# bbaudio.net
KiCad netlist of a schematic drawn in EAGLE
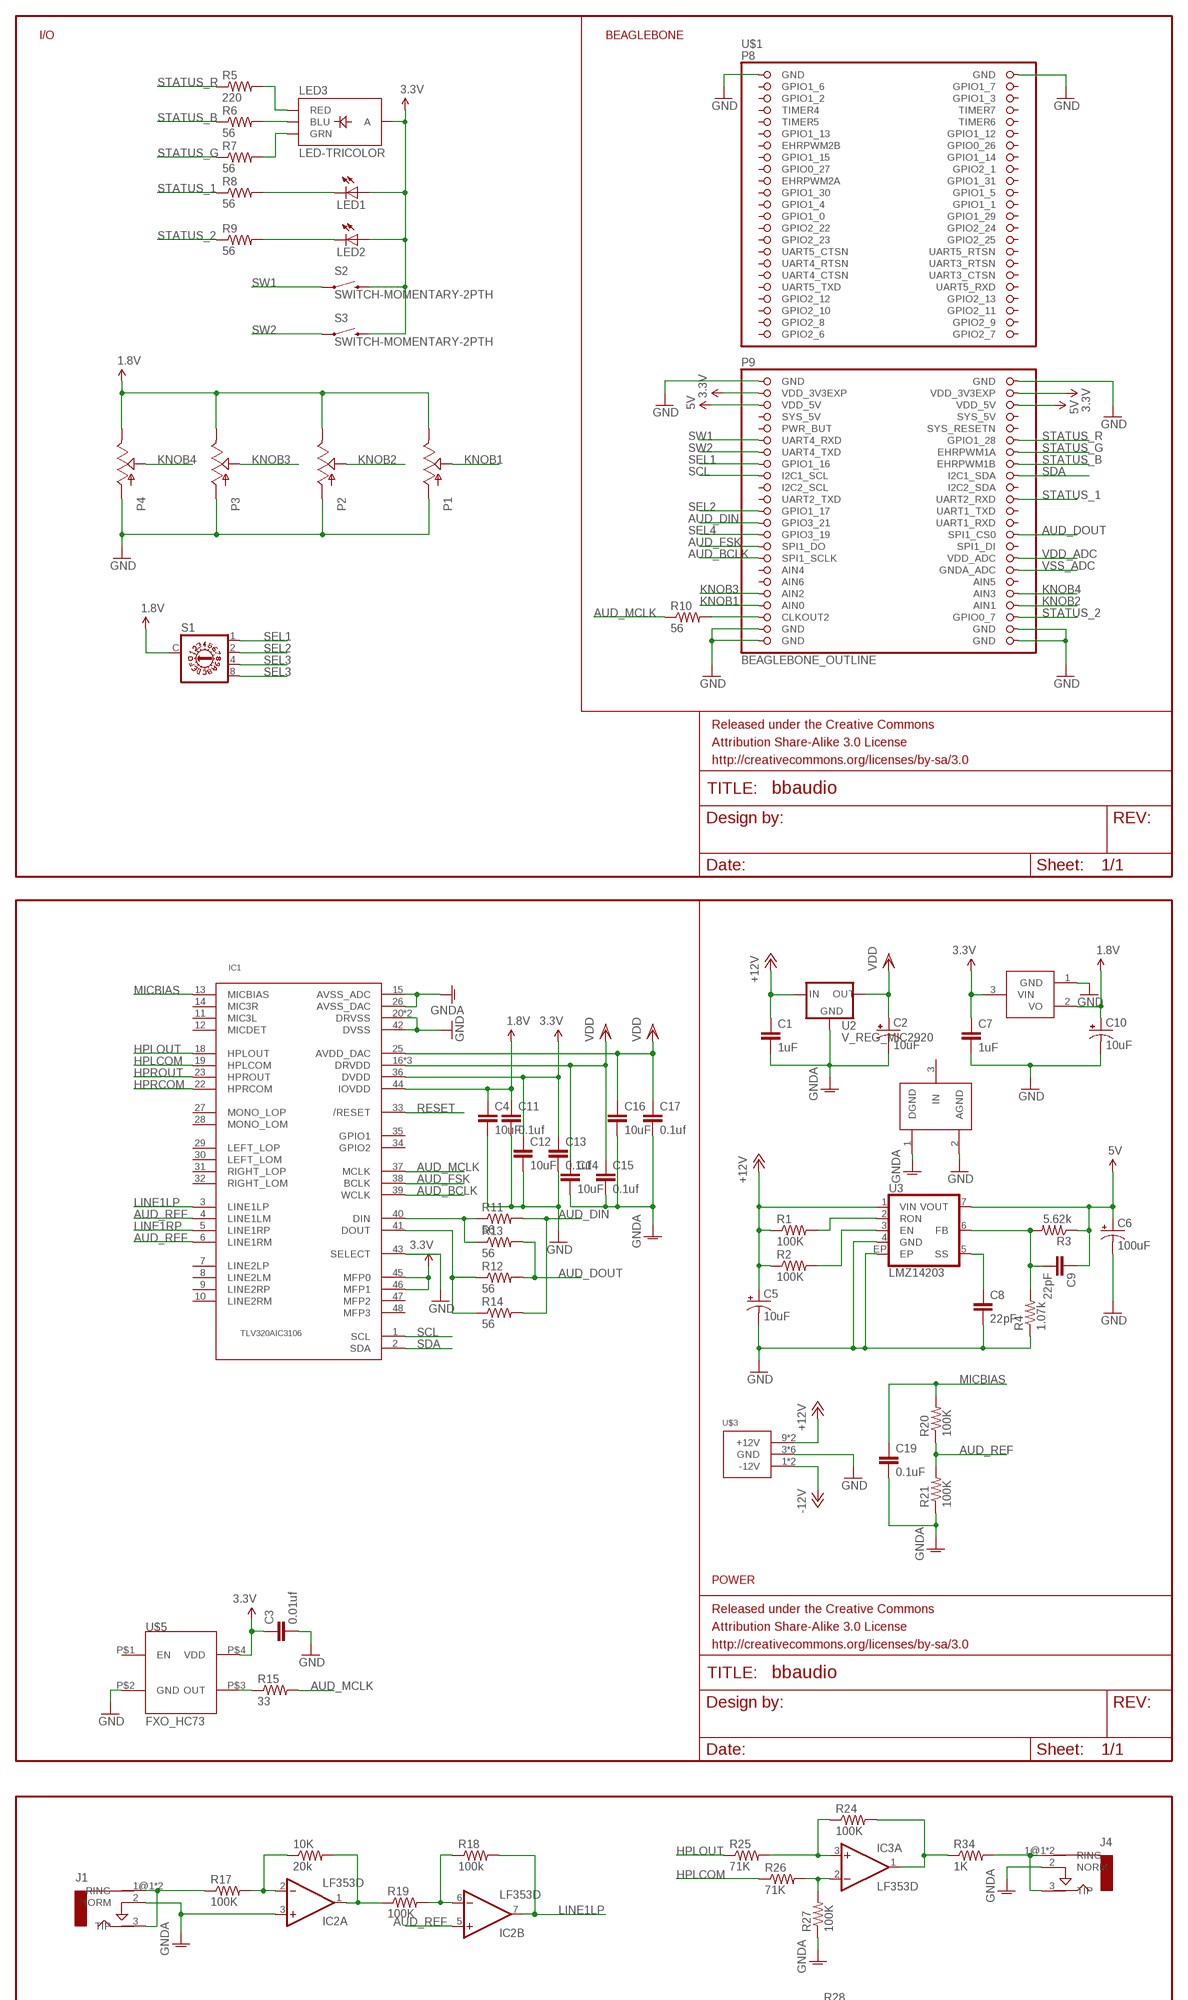
[diagram p0: schematic, sheet 1, part 1 of 2]
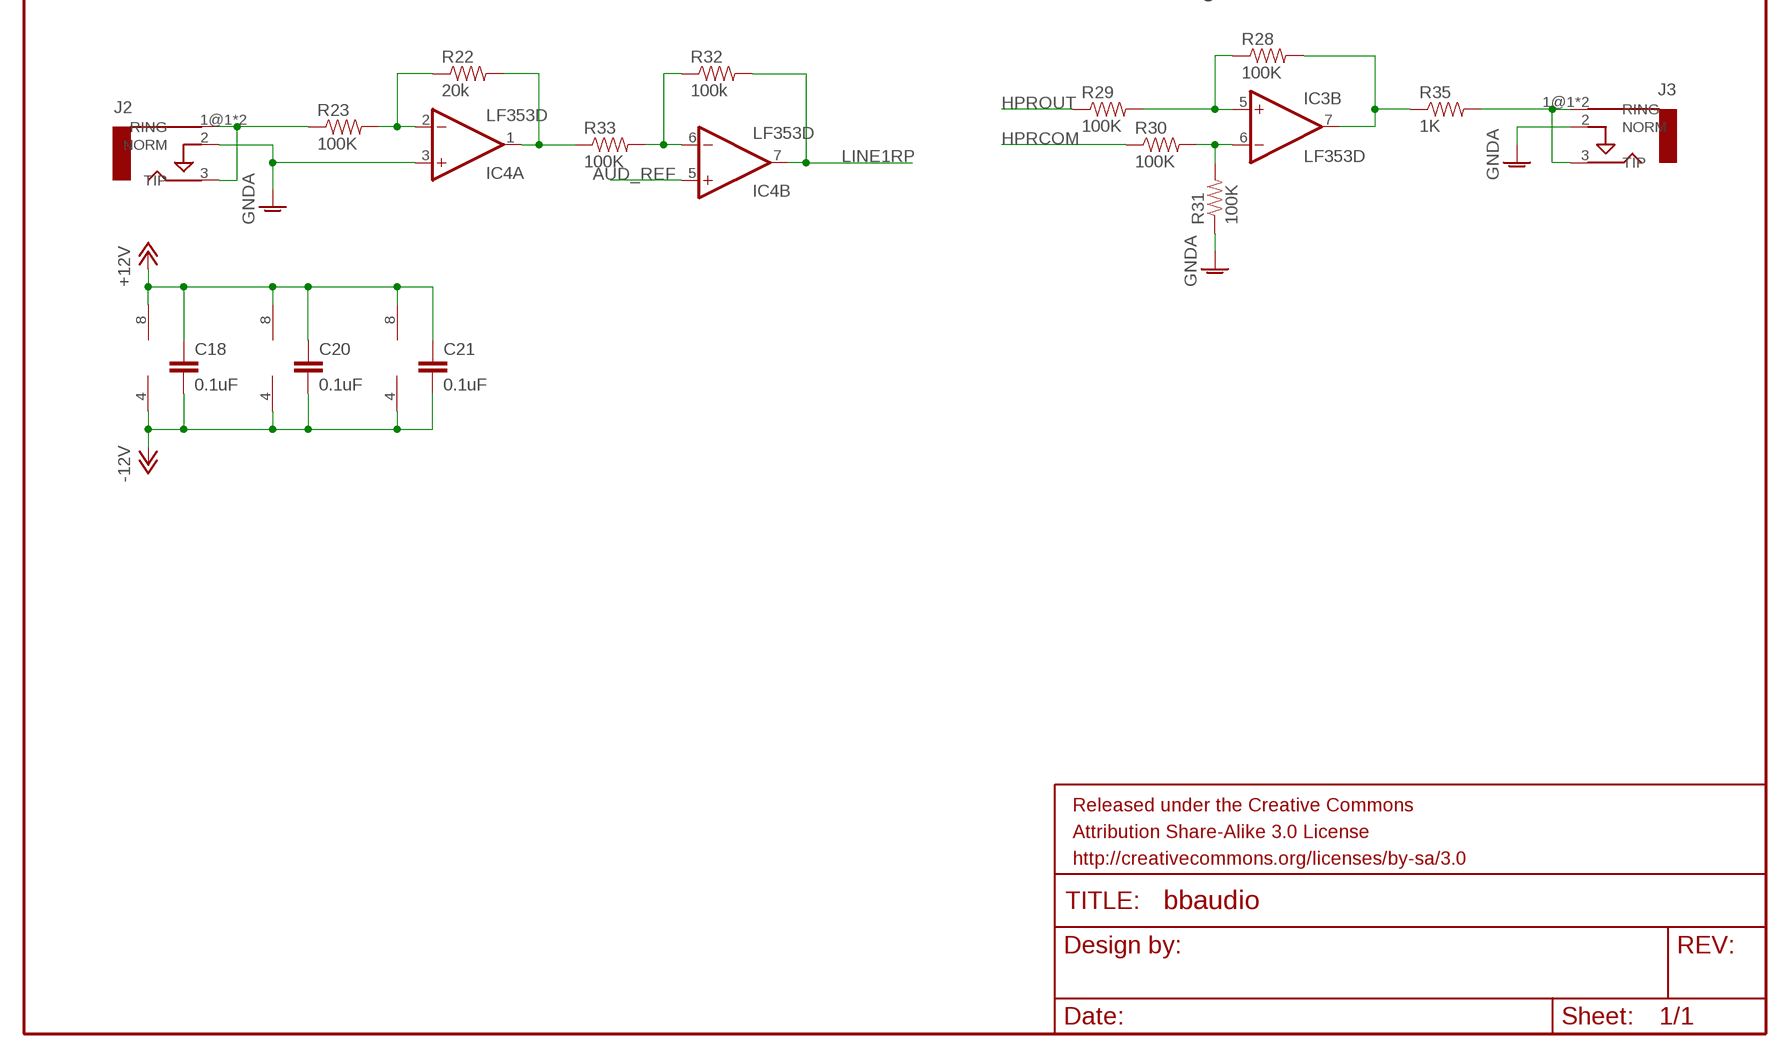
[diagram p1: schematic, sheet 1, part 2 of 2]

(export (version "E")
  (design (tool "Eeschema 10.0.6"))
  (components
    (comp (ref "10K")
      (value "20k")
      (footprint "eagle-import:0603-RES")
      (libsource (lib "eagle-import") (part "RESISTOR0603-RES"))
    )
    (comp (ref "C1")
      (value "1uF")
      (footprint "eagle-import:C0603")
      (libsource (lib "eagle-import") (part "C-EUC0603"))
    )
    (comp (ref "C2")
      (value "10uF")
      (footprint "eagle-import:EIA3216")
      (libsource (lib "eagle-import") (part "CAP_POL1206"))
    )
    (comp (ref "C3")
      (value "0.01uf")
      (footprint "eagle-import:C0603")
      (libsource (lib "eagle-import") (part "C-EUC0603"))
    )
    (comp (ref "C4")
      (value "10uF")
      (footprint "eagle-import:C0603")
      (libsource (lib "eagle-import") (part "C-EUC0603"))
    )
    (comp (ref "C5")
      (value "10uF")
      (footprint "eagle-import:EIA3216")
      (libsource (lib "eagle-import") (part "CAP_POL1206"))
    )
    (comp (ref "C6")
      (value "100uF")
      (footprint "eagle-import:EIA3216")
      (libsource (lib "eagle-import") (part "CAP_POL1206"))
    )
    (comp (ref "C7")
      (value "1uF")
      (footprint "eagle-import:C0603")
      (libsource (lib "eagle-import") (part "C-EUC0603"))
    )
    (comp (ref "C8")
      (value "22pF")
      (footprint "eagle-import:C0603")
      (libsource (lib "eagle-import") (part "C-EUC0603"))
    )
    (comp (ref "C9")
      (value "22pF")
      (footprint "eagle-import:C0603")
      (libsource (lib "eagle-import") (part "C-EUC0603"))
    )
    (comp (ref "C10")
      (value "10uF")
      (footprint "eagle-import:EIA3216")
      (libsource (lib "eagle-import") (part "CAP_POL1206"))
    )
    (comp (ref "C11")
      (value "0.1uf")
      (footprint "eagle-import:C0603")
      (libsource (lib "eagle-import") (part "C-EUC0603"))
    )
    (comp (ref "C12")
      (value "10uF")
      (footprint "eagle-import:C0603")
      (libsource (lib "eagle-import") (part "C-EUC0603"))
    )
    (comp (ref "C13")
      (value "0.1uf")
      (footprint "eagle-import:C0603")
      (libsource (lib "eagle-import") (part "C-EUC0603"))
    )
    (comp (ref "C14")
      (value "10uF")
      (footprint "eagle-import:C0603")
      (libsource (lib "eagle-import") (part "C-EUC0603"))
    )
    (comp (ref "C15")
      (value "0.1uf")
      (footprint "eagle-import:C0603")
      (libsource (lib "eagle-import") (part "C-EUC0603"))
    )
    (comp (ref "C16")
      (value "10uF")
      (footprint "eagle-import:C0603")
      (libsource (lib "eagle-import") (part "C-EUC0603"))
    )
    (comp (ref "C17")
      (value "0.1uf")
      (footprint "eagle-import:C0603")
      (libsource (lib "eagle-import") (part "C-EUC0603"))
    )
    (comp (ref "C18")
      (value "0.1uF")
      (footprint "eagle-import:C0603")
      (libsource (lib "eagle-import") (part "C-EUC0603"))
    )
    (comp (ref "C19")
      (value "0.1uF")
      (footprint "eagle-import:C0603")
      (libsource (lib "eagle-import") (part "C-EUC0603"))
    )
    (comp (ref "C20")
      (value "0.1uF")
      (footprint "eagle-import:C0603")
      (libsource (lib "eagle-import") (part "C-EUC0603"))
    )
    (comp (ref "C21")
      (value "0.1uF")
      (footprint "eagle-import:C0603")
      (libsource (lib "eagle-import") (part "C-EUC0603"))
    )
    (comp (ref "IC1")
      (value "TLV320AIC3106")
      (footprint "eagle-import:QFN48")
      (libsource (lib "eagle-import") (part "TLV320AIC3106"))
    )
    (comp (ref "IC2")
      (value "LF353D")
      (footprint "eagle-import:SO08")
      (libsource (lib "eagle-import") (part "LF353D"))
    )
    (comp (ref "IC3")
      (value "LF353D")
      (footprint "eagle-import:SO08")
      (libsource (lib "eagle-import") (part "LF353D"))
    )
    (comp (ref "IC4")
      (value "LF353D")
      (footprint "eagle-import:SO08")
      (libsource (lib "eagle-import") (part "LF353D"))
    )
    (comp (ref "J1")
      (value "AUDIO-JACKERTHENVAR")
      (footprint "eagle-import:ERTHENVAR-JACK")
      (libsource (lib "eagle-import") (part "AUDIO-JACKERTHENVAR"))
    )
    (comp (ref "J2")
      (value "AUDIO-JACKERTHENVAR")
      (footprint "eagle-import:ERTHENVAR-JACK")
      (libsource (lib "eagle-import") (part "AUDIO-JACKERTHENVAR"))
    )
    (comp (ref "J3")
      (value "AUDIO-JACKERTHENVAR")
      (footprint "eagle-import:ERTHENVAR-JACK")
      (libsource (lib "eagle-import") (part "AUDIO-JACKERTHENVAR"))
    )
    (comp (ref "J4")
      (value "AUDIO-JACKERTHENVAR")
      (footprint "eagle-import:ERTHENVAR-JACK")
      (libsource (lib "eagle-import") (part "AUDIO-JACKERTHENVAR"))
    )
    (comp (ref "LED1")
      (value "LED-FKIT-1206")
      (footprint "eagle-import:FKIT-LED-1206")
      (libsource (lib "eagle-import") (part "LED-FKIT-1206"))
    )
    (comp (ref "LED2")
      (value "LED-FKIT-1206")
      (footprint "eagle-import:FKIT-LED-1206")
      (libsource (lib "eagle-import") (part "LED-FKIT-1206"))
    )
    (comp (ref "LED3")
      (value "LED-TRICOLOR")
      (footprint "eagle-import:LED-TRICOLOR-SMD")
      (libsource (lib "eagle-import") (part "LED-TRICOLOR"))
    )
    (comp (ref "P1")
      (value "SPARKFUN_POTPDB12")
      (footprint "eagle-import:SPARKFUN_PDB12")
      (libsource (lib "eagle-import") (part "SPARKFUN_POTPDB12"))
    )
    (comp (ref "P2")
      (value "SPARKFUN_POTPDB12")
      (footprint "eagle-import:SPARKFUN_PDB12")
      (libsource (lib "eagle-import") (part "SPARKFUN_POTPDB12"))
    )
    (comp (ref "P3")
      (value "SPARKFUN_POTPDB12")
      (footprint "eagle-import:SPARKFUN_PDB12")
      (libsource (lib "eagle-import") (part "SPARKFUN_POTPDB12"))
    )
    (comp (ref "P4")
      (value "SPARKFUN_POTPDB12")
      (footprint "eagle-import:SPARKFUN_PDB12")
      (libsource (lib "eagle-import") (part "SPARKFUN_POTPDB12"))
    )
    (comp (ref "R1")
      (value "100K")
      (footprint "eagle-import:0603-RES")
      (libsource (lib "eagle-import") (part "RESISTOR0603-RES"))
    )
    (comp (ref "R2")
      (value "100K")
      (footprint "eagle-import:0603-RES")
      (libsource (lib "eagle-import") (part "RESISTOR0603-RES"))
    )
    (comp (ref "R3")
      (value "5.62k")
      (footprint "eagle-import:0603-RES")
      (libsource (lib "eagle-import") (part "RESISTOR0603-RES"))
    )
    (comp (ref "R4")
      (value "1.07k")
      (footprint "eagle-import:0603-RES")
      (libsource (lib "eagle-import") (part "RESISTOR0603-RES"))
    )
    (comp (ref "R5")
      (value "220")
      (footprint "eagle-import:0603-RES")
      (libsource (lib "eagle-import") (part "RESISTOR0603-RES"))
    )
    (comp (ref "R6")
      (value "56")
      (footprint "eagle-import:0603-RES")
      (libsource (lib "eagle-import") (part "RESISTOR0603-RES"))
    )
    (comp (ref "R7")
      (value "56")
      (footprint "eagle-import:0603-RES")
      (libsource (lib "eagle-import") (part "RESISTOR0603-RES"))
    )
    (comp (ref "R8")
      (value "56")
      (footprint "eagle-import:0603-RES")
      (libsource (lib "eagle-import") (part "RESISTOR0603-RES"))
    )
    (comp (ref "R9")
      (value "56")
      (footprint "eagle-import:0603-RES")
      (libsource (lib "eagle-import") (part "RESISTOR0603-RES"))
    )
    (comp (ref "R10")
      (value "56")
      (footprint "eagle-import:0603-RES")
      (libsource (lib "eagle-import") (part "RESISTOR0603-RES"))
    )
    (comp (ref "R11")
      (value "56")
      (footprint "eagle-import:0603-RES")
      (libsource (lib "eagle-import") (part "RESISTOR0603-RES"))
    )
    (comp (ref "R12")
      (value "56")
      (footprint "eagle-import:0603-RES")
      (libsource (lib "eagle-import") (part "RESISTOR0603-RES"))
    )
    (comp (ref "R13")
      (value "56")
      (footprint "eagle-import:0603-RES")
      (libsource (lib "eagle-import") (part "RESISTOR0603-RES"))
    )
    (comp (ref "R14")
      (value "56")
      (footprint "eagle-import:0603-RES")
      (libsource (lib "eagle-import") (part "RESISTOR0603-RES"))
    )
    (comp (ref "R15")
      (value "33")
      (footprint "eagle-import:0603-RES")
      (libsource (lib "eagle-import") (part "RESISTOR0603-RES"))
    )
    (comp (ref "R17")
      (value "100K")
      (footprint "eagle-import:0603-RES")
      (libsource (lib "eagle-import") (part "RESISTOR0603-RES"))
    )
    (comp (ref "R18")
      (value "100k")
      (footprint "eagle-import:0603-RES")
      (libsource (lib "eagle-import") (part "RESISTOR0603-RES"))
    )
    (comp (ref "R19")
      (value "100K")
      (footprint "eagle-import:0603-RES")
      (libsource (lib "eagle-import") (part "RESISTOR0603-RES"))
    )
    (comp (ref "R20")
      (value "100K")
      (footprint "eagle-import:0603-RES")
      (libsource (lib "eagle-import") (part "RESISTOR0603-RES"))
    )
    (comp (ref "R21")
      (value "100K")
      (footprint "eagle-import:0603-RES")
      (libsource (lib "eagle-import") (part "RESISTOR0603-RES"))
    )
    (comp (ref "R22")
      (value "20k")
      (footprint "eagle-import:0603-RES")
      (libsource (lib "eagle-import") (part "RESISTOR0603-RES"))
    )
    (comp (ref "R23")
      (value "100K")
      (footprint "eagle-import:0603-RES")
      (libsource (lib "eagle-import") (part "RESISTOR0603-RES"))
    )
    (comp (ref "R24")
      (value "100K")
      (footprint "eagle-import:0603-RES")
      (libsource (lib "eagle-import") (part "RESISTOR0603-RES"))
    )
    (comp (ref "R25")
      (value "71K")
      (footprint "eagle-import:0603-RES")
      (libsource (lib "eagle-import") (part "RESISTOR0603-RES"))
    )
    (comp (ref "R26")
      (value "71K")
      (footprint "eagle-import:0603-RES")
      (libsource (lib "eagle-import") (part "RESISTOR0603-RES"))
    )
    (comp (ref "R27")
      (value "100K")
      (footprint "eagle-import:0603-RES")
      (libsource (lib "eagle-import") (part "RESISTOR0603-RES"))
    )
    (comp (ref "R28")
      (value "100K")
      (footprint "eagle-import:0603-RES")
      (libsource (lib "eagle-import") (part "RESISTOR0603-RES"))
    )
    (comp (ref "R29")
      (value "100K")
      (footprint "eagle-import:0603-RES")
      (libsource (lib "eagle-import") (part "RESISTOR0603-RES"))
    )
    (comp (ref "R30")
      (value "100K")
      (footprint "eagle-import:0603-RES")
      (libsource (lib "eagle-import") (part "RESISTOR0603-RES"))
    )
    (comp (ref "R31")
      (value "100K")
      (footprint "eagle-import:0603-RES")
      (libsource (lib "eagle-import") (part "RESISTOR0603-RES"))
    )
    (comp (ref "R32")
      (value "100k")
      (footprint "eagle-import:0603-RES")
      (libsource (lib "eagle-import") (part "RESISTOR0603-RES"))
    )
    (comp (ref "R33")
      (value "100K")
      (footprint "eagle-import:0603-RES")
      (libsource (lib "eagle-import") (part "RESISTOR0603-RES"))
    )
    (comp (ref "R34")
      (value "1K")
      (footprint "eagle-import:0603-RES")
      (libsource (lib "eagle-import") (part "RESISTOR0603-RES"))
    )
    (comp (ref "R35")
      (value "1K")
      (footprint "eagle-import:0603-RES")
      (libsource (lib "eagle-import") (part "RESISTOR0603-RES"))
    )
    (comp (ref "S1")
      (value "P103")
      (footprint "eagle-import:P103")
      (libsource (lib "eagle-import") (part "P103"))
    )
    (comp (ref "S2")
      (value "SWITCH-MOMENTARY-2PTH")
      (footprint "eagle-import:TACTILE-PTH")
      (libsource (lib "eagle-import") (part "SWITCH-MOMENTARY-2PTH"))
    )
    (comp (ref "S3")
      (value "SWITCH-MOMENTARY-2PTH")
      (footprint "eagle-import:TACTILE-PTH")
      (libsource (lib "eagle-import") (part "SWITCH-MOMENTARY-2PTH"))
    )
    (comp (ref "U$1")
      (value "BEAGLEBONE_OUTLINE")
      (footprint "eagle-import:BEAGLEBONE_SHIELD")
      (libsource (lib "eagle-import") (part "BEAGLEBONE_OUTLINE"))
    )
    (comp (ref "U$3")
      (value "POWER_SIMPLE10")
      (footprint "eagle-import:POWER_10")
      (libsource (lib "eagle-import") (part "POWER_SIMPLE10"))
    )
    (comp (ref "U$5")
      (value "FXO_HC73")
      (footprint "eagle-import:4PIN")
      (libsource (lib "eagle-import") (part "FXO_HC73"))
    )
    (comp (ref "U$11")
      (value "GND_CONNECT")
      (footprint "eagle-import:GND_CONNECT")
      (libsource (lib "eagle-import") (part "GND_CONNECT"))
    )
    (comp (ref "U2")
      (value "V_REG_MIC2920")
      (footprint "eagle-import:SOT223")
      (libsource (lib "eagle-import") (part "V_REG_MIC2920"))
    )
    (comp (ref "U3")
      (value "LMZ14203")
      (footprint "eagle-import:TO-PMOD-7")
      (libsource (lib "eagle-import") (part "LMZ14203"))
    )
    (comp (ref "U4")
      (value "VREG")
      (footprint "eagle-import:SOT23-3")
      (libsource (lib "eagle-import") (part "VREG"))
    )
  )
  (nets
    (net (code "1") (name "+12V") (class "Default")
      (node (ref "C1") (pin "1") (pinfunction "1_1") (pintype "passive"))
      (node (ref "C18") (pin "1") (pinfunction "1_1") (pintype "passive"))
      (node (ref "C20") (pin "1") (pinfunction "1_1") (pintype "passive"))
      (node (ref "C21") (pin "1") (pinfunction "1_1") (pintype "passive"))
      (node (ref "C5") (pin "A") (pinfunction "+_A") (pintype "passive"))
      (node (ref "IC2") (pin "8") (pinfunction "V+_8") (pintype "power_in"))
      (node (ref "IC3") (pin "8") (pinfunction "V+_8") (pintype "power_in"))
      (node (ref "IC4") (pin "8") (pinfunction "V+_8") (pintype "power_in"))
      (node (ref "R1") (pin "1") (pinfunction "1_1") (pintype "passive"))
      (node (ref "R2") (pin "1") (pinfunction "1_1") (pintype "passive"))
      (node (ref "U$3") (pin "10") (pinfunction "+12V_10") (pintype "bidirectional"))
      (node (ref "U$3") (pin "9") (pinfunction "+12V_9") (pintype "bidirectional"))
      (node (ref "U2") (pin "1") (pinfunction "IN_1") (pintype "input"))
      (node (ref "U3") (pin "1") (pinfunction "VIN_1") (pintype "bidirectional"))
    )
    (net (code "2") (name "-12V") (class "Default")
      (node (ref "C18") (pin "2") (pinfunction "2_2") (pintype "passive"))
      (node (ref "C20") (pin "2") (pinfunction "2_2") (pintype "passive"))
      (node (ref "C21") (pin "2") (pinfunction "2_2") (pintype "passive"))
      (node (ref "IC2") (pin "4") (pinfunction "V-_4") (pintype "power_in"))
      (node (ref "IC3") (pin "4") (pinfunction "V-_4") (pintype "power_in"))
      (node (ref "IC4") (pin "4") (pinfunction "V-_4") (pintype "power_in"))
      (node (ref "U$3") (pin "1") (pinfunction "-12V_1") (pintype "bidirectional"))
      (node (ref "U$3") (pin "2") (pinfunction "-12V_2") (pintype "bidirectional"))
    )
    (net (code "3") (name "/AUD_BCLK") (class "Default")
      (node (ref "IC1") (pin "39") (pinfunction "WCLK_39") (pintype "bidirectional"))
      (node (ref "U$1") (pin "77") (pinfunction "SPI1_SCLK_77") (pintype "passive"))
    )
    (net (code "4") (name "/AUD_DIN") (class "Default")
      (node (ref "R11") (pin "2") (pinfunction "2_2") (pintype "passive"))
      (node (ref "R14") (pin "2") (pinfunction "2_2") (pintype "passive"))
      (node (ref "U$1") (pin "71") (pinfunction "GPIO3_21_71") (pintype "passive"))
    )
    (net (code "5") (name "/AUD_DOUT") (class "Default")
      (node (ref "R12") (pin "2") (pinfunction "2_2") (pintype "passive"))
      (node (ref "R13") (pin "2") (pinfunction "2_2") (pintype "passive"))
      (node (ref "U$1") (pin "74") (pinfunction "SPI1_CS0_74") (pintype "passive"))
    )
    (net (code "6") (name "/AUD_FSK") (class "Default")
      (node (ref "IC1") (pin "38") (pinfunction "BCLK_38") (pintype "bidirectional"))
      (node (ref "U$1") (pin "75") (pinfunction "SPI1_DO_75") (pintype "passive"))
    )
    (net (code "7") (name "/AUD_MCLK") (class "Default")
      (node (ref "IC1") (pin "37") (pinfunction "MCLK_37") (pintype "bidirectional"))
      (node (ref "R10") (pin "1") (pinfunction "1_1") (pintype "passive"))
      (node (ref "R15") (pin "2") (pinfunction "2_2") (pintype "passive"))
    )
    (net (code "8") (name "/AUD_REF") (class "Default")
      (node (ref "IC1") (pin "4") (pinfunction "LINE1LM_4") (pintype "bidirectional"))
      (node (ref "IC1") (pin "6") (pinfunction "LINE1RM_6") (pintype "bidirectional"))
      (node (ref "IC2") (pin "5") (pinfunction "+IN_5") (pintype "input"))
      (node (ref "IC4") (pin "5") (pinfunction "+IN_5") (pintype "input"))
      (node (ref "R20") (pin "1") (pinfunction "1_1") (pintype "passive"))
      (node (ref "R21") (pin "2") (pinfunction "2_2") (pintype "passive"))
    )
    (net (code "9") (name "/HPLCOM") (class "Default")
      (node (ref "IC1") (pin "19") (pinfunction "HPLCOM_19") (pintype "bidirectional"))
      (node (ref "R26") (pin "1") (pinfunction "1_1") (pintype "passive"))
    )
    (net (code "10") (name "/HPLOUT") (class "Default")
      (node (ref "IC1") (pin "18") (pinfunction "HPLOUT_18") (pintype "bidirectional"))
      (node (ref "R25") (pin "1") (pinfunction "1_1") (pintype "passive"))
    )
    (net (code "11") (name "/HPRCOM") (class "Default")
      (node (ref "IC1") (pin "22") (pinfunction "HPRCOM_22") (pintype "bidirectional"))
      (node (ref "R30") (pin "1") (pinfunction "1_1") (pintype "passive"))
    )
    (net (code "12") (name "/HPROUT") (class "Default")
      (node (ref "IC1") (pin "23") (pinfunction "HPROUT_23") (pintype "bidirectional"))
      (node (ref "R29") (pin "1") (pinfunction "1_1") (pintype "passive"))
    )
    (net (code "13") (name "/KNOB1") (class "Default")
      (node (ref "P1") (pin "2") (pinfunction "S_2") (pintype "passive"))
      (node (ref "U$1") (pin "85") (pinfunction "AIN0_85") (pintype "power_in"))
    )
    (net (code "14") (name "/KNOB2") (class "Default")
      (node (ref "P2") (pin "2") (pinfunction "S_2") (pintype "passive"))
      (node (ref "U$1") (pin "86") (pinfunction "AIN1_86") (pintype "passive"))
    )
    (net (code "15") (name "/KNOB3") (class "Default")
      (node (ref "P3") (pin "2") (pinfunction "S_2") (pintype "passive"))
      (node (ref "U$1") (pin "83") (pinfunction "AIN2_83") (pintype "passive"))
    )
    (net (code "16") (name "/KNOB4") (class "Default")
      (node (ref "P4") (pin "2") (pinfunction "S_2") (pintype "passive"))
      (node (ref "U$1") (pin "84") (pinfunction "AIN3_84") (pintype "passive"))
    )
    (net (code "17") (name "/LINE1LP") (class "Default")
      (node (ref "IC1") (pin "3") (pinfunction "LINE1LP_3") (pintype "bidirectional"))
      (node (ref "IC2") (pin "7") (pinfunction "OUT_7") (pintype "output"))
      (node (ref "R18") (pin "2") (pinfunction "2_2") (pintype "passive"))
    )
    (net (code "18") (name "/LINE1RP") (class "Default")
      (node (ref "IC1") (pin "5") (pinfunction "LINE1RP_5") (pintype "bidirectional"))
      (node (ref "IC4") (pin "7") (pinfunction "OUT_7") (pintype "output"))
      (node (ref "R32") (pin "2") (pinfunction "2_2") (pintype "passive"))
    )
    (net (code "19") (name "/MICBIAS") (class "Default")
      (node (ref "C19") (pin "1") (pinfunction "1_1") (pintype "passive"))
      (node (ref "IC1") (pin "13") (pinfunction "MICBIAS_13") (pintype "bidirectional"))
      (node (ref "R20") (pin "2") (pinfunction "2_2") (pintype "passive"))
    )
    (net (code "20") (name "/RESET") (class "Default")
      (node (ref "IC1") (pin "33") (pinfunction "/RESET_33") (pintype "bidirectional"))
    )
    (net (code "21") (name "/SCL") (class "Default")
      (node (ref "IC1") (pin "1") (pinfunction "SCL_1") (pintype "bidirectional"))
      (node (ref "U$1") (pin "63") (pinfunction "I2C1_SCL_63") (pintype "passive"))
    )
    (net (code "22") (name "/SDA") (class "Default")
      (node (ref "IC1") (pin "2") (pinfunction "SDA_2") (pintype "bidirectional"))
      (node (ref "U$1") (pin "64") (pinfunction "I2C1_SDA_64") (pintype "passive"))
    )
    (net (code "23") (name "/SEL1") (class "Default")
      (node (ref "S1") (pin "1") (pinfunction "1_1") (pintype "passive"))
      (node (ref "U$1") (pin "61") (pinfunction "GPIO1_16_61") (pintype "passive"))
    )
    (net (code "24") (name "/SEL2") (class "Default")
      (node (ref "S1") (pin "2") (pinfunction "2_2") (pintype "passive"))
      (node (ref "U$1") (pin "69") (pinfunction "GPIO1_17_69") (pintype "passive"))
    )
    (net (code "25") (name "/SEL3") (class "Default")
      (node (ref "S1") (pin "4") (pinfunction "4_4") (pintype "passive"))
    )
    (net (code "26") (name "/SEL4") (class "Default")
      (node (ref "S1") (pin "8") (pinfunction "8_8") (pintype "passive"))
      (node (ref "U$1") (pin "73") (pinfunction "GPIO3_19_73") (pintype "passive"))
    )
    (net (code "27") (name "/STATUS_1") (class "Default")
      (node (ref "R8") (pin "1") (pinfunction "1_1") (pintype "passive"))
      (node (ref "U$1") (pin "68") (pinfunction "UART2_RXD_68") (pintype "passive"))
    )
    (net (code "28") (name "/STATUS_2") (class "Default")
      (node (ref "R9") (pin "1") (pinfunction "1_1") (pintype "passive"))
      (node (ref "U$1") (pin "88") (pinfunction "GPIO0_7_88") (pintype "passive"))
    )
    (net (code "29") (name "/STATUS_B") (class "Default")
      (node (ref "R6") (pin "1") (pinfunction "1_1") (pintype "passive"))
      (node (ref "U$1") (pin "62") (pinfunction "EHRPWM1B_62") (pintype "passive"))
    )
    (net (code "30") (name "/STATUS_G") (class "Default")
      (node (ref "R7") (pin "1") (pinfunction "1_1") (pintype "passive"))
      (node (ref "U$1") (pin "60") (pinfunction "EHRPWM1A_60") (pintype "passive"))
    )
    (net (code "31") (name "/STATUS_R") (class "Default")
      (node (ref "R5") (pin "1") (pinfunction "1_1") (pintype "passive"))
      (node (ref "U$1") (pin "58") (pinfunction "GPIO1_28_58") (pintype "passive"))
    )
    (net (code "32") (name "/SW1") (class "Default")
      (node (ref "S2") (pin "1") (pinfunction "1_1") (pintype "passive"))
      (node (ref "U$1") (pin "57") (pinfunction "UART4_RXD_57") (pintype "passive"))
    )
    (net (code "33") (name "/SW2") (class "Default")
      (node (ref "S3") (pin "1") (pinfunction "1_1") (pintype "passive"))
      (node (ref "U$1") (pin "59") (pinfunction "UART4_TXD_59") (pintype "passive"))
    )
    (net (code "34") (name "/SYS_5V") (class "Default")
      (node (ref "U$1") (pin "53") (pinfunction "SYS_5V_53") (pintype "power_in"))
    )
    (net (code "35") (name "/VDD_ADC") (class "Default")
      (node (ref "U$1") (pin "78") (pinfunction "VDD_ADC_78") (pintype "passive"))
    )
    (net (code "36") (name "/VSS_ADC") (class "Default")
      (node (ref "U$1") (pin "80") (pinfunction "GNDA_ADC_80") (pintype "passive"))
    )
    (net (code "37") (name "1.8V") (class "Default")
      (node (ref "C10") (pin "A") (pinfunction "+_A") (pintype "passive"))
      (node (ref "C11") (pin "1") (pinfunction "1_1") (pintype "passive"))
      (node (ref "C4") (pin "1") (pinfunction "1_1") (pintype "passive"))
      (node (ref "IC1") (pin "44") (pinfunction "IOVDD_44") (pintype "bidirectional"))
      (node (ref "P1") (pin "3") (pinfunction "E_3") (pintype "passive"))
      (node (ref "P2") (pin "3") (pinfunction "E_3") (pintype "passive"))
      (node (ref "P3") (pin "3") (pinfunction "E_3") (pintype "passive"))
      (node (ref "P4") (pin "3") (pinfunction "E_3") (pintype "passive"))
      (node (ref "S1") (pin "C") (pinfunction "C_C") (pintype "passive"))
      (node (ref "U4") (pin "2") (pinfunction "VO_2") (pintype "bidirectional"))
    )
    (net (code "38") (name "3.3V") (class "Default")
      (node (ref "C12") (pin "1") (pinfunction "1_1") (pintype "passive"))
      (node (ref "C13") (pin "1") (pinfunction "1_1") (pintype "passive"))
      (node (ref "C3") (pin "1") (pinfunction "1_1") (pintype "passive"))
      (node (ref "C7") (pin "1") (pinfunction "1_1") (pintype "passive"))
      (node (ref "IC1") (pin "36") (pinfunction "DVDD_36") (pintype "bidirectional"))
      (node (ref "IC1") (pin "45") (pinfunction "MFP0_45") (pintype "bidirectional"))
      (node (ref "IC1") (pin "46") (pinfunction "MFP1_46") (pintype "bidirectional"))
      (node (ref "LED1") (pin "A") (pinfunction "A_A") (pintype "passive"))
      (node (ref "LED2") (pin "A") (pinfunction "A_A") (pintype "passive"))
      (node (ref "LED3") (pin "A") (pinfunction "A_A") (pintype "bidirectional"))
      (node (ref "S2") (pin "3") (pinfunction "2_3") (pintype "passive"))
      (node (ref "S3") (pin "3") (pinfunction "2_3") (pintype "passive"))
      (node (ref "U$1") (pin "49") (pinfunction "VDD_3V3EXP_49") (pintype "power_in"))
      (node (ref "U$1") (pin "50") (pinfunction "VDD_3V3EXP_50") (pintype "power_in"))
      (node (ref "U$5") (pin "P$4") (pinfunction "VDD_P$4") (pintype "bidirectional"))
      (node (ref "U4") (pin "3") (pinfunction "VIN_3") (pintype "bidirectional"))
    )
    (net (code "39") (name "5V") (class "Default")
      (node (ref "C6") (pin "A") (pinfunction "+_A") (pintype "passive"))
      (node (ref "C9") (pin "1") (pinfunction "1_1") (pintype "passive"))
      (node (ref "R3") (pin "1") (pinfunction "1_1") (pintype "passive"))
      (node (ref "U$1") (pin "51") (pinfunction "VDD_5V_51") (pintype "power_in"))
      (node (ref "U$1") (pin "52") (pinfunction "VDD_5V_52") (pintype "power_in"))
      (node (ref "U3") (pin "7") (pinfunction "VOUT_7") (pintype "bidirectional"))
    )
    (net (code "40") (name "GND") (class "Default")
      (node (ref "C10") (pin "C") (pinfunction "-_C") (pintype "passive"))
      (node (ref "C11") (pin "2") (pinfunction "2_2") (pintype "passive"))
      (node (ref "C12") (pin "2") (pinfunction "2_2") (pintype "passive"))
      (node (ref "C13") (pin "2") (pinfunction "2_2") (pintype "passive"))
      (node (ref "C3") (pin "2") (pinfunction "2_2") (pintype "passive"))
      (node (ref "C4") (pin "2") (pinfunction "2_2") (pintype "passive"))
      (node (ref "C5") (pin "C") (pinfunction "-_C") (pintype "passive"))
      (node (ref "C6") (pin "C") (pinfunction "-_C") (pintype "passive"))
      (node (ref "C7") (pin "2") (pinfunction "2_2") (pintype "passive"))
      (node (ref "C8") (pin "2") (pinfunction "2_2") (pintype "passive"))
      (node (ref "IC1") (pin "20") (pinfunction "DRVSS_20") (pintype "bidirectional"))
      (node (ref "IC1") (pin "21") (pinfunction "DRVSS_21") (pintype "bidirectional"))
      (node (ref "IC1") (pin "42") (pinfunction "DVSS_42") (pintype "bidirectional"))
      (node (ref "IC1") (pin "43") (pinfunction "SELECT_43") (pintype "bidirectional"))
      (node (ref "P1") (pin "1") (pinfunction "A_1") (pintype "passive"))
      (node (ref "P2") (pin "1") (pinfunction "A_1") (pintype "passive"))
      (node (ref "P3") (pin "1") (pinfunction "A_1") (pintype "passive"))
      (node (ref "P4") (pin "1") (pinfunction "A_1") (pintype "passive"))
      (node (ref "R4") (pin "1") (pinfunction "1_1") (pintype "passive"))
      (node (ref "U$1") (pin "1") (pinfunction "GND_1") (pintype "power_in"))
      (node (ref "U$1") (pin "2") (pinfunction "GND_2") (pintype "power_in"))
      (node (ref "U$1") (pin "47") (pinfunction "GND_47") (pintype "power_in"))
      (node (ref "U$1") (pin "48") (pinfunction "GND_48") (pintype "power_in"))
      (node (ref "U$1") (pin "89") (pinfunction "GND_89") (pintype "power_in"))
      (node (ref "U$1") (pin "90") (pinfunction "GND_90") (pintype "power_in"))
      (node (ref "U$1") (pin "91") (pinfunction "GND_91") (pintype "power_in"))
      (node (ref "U$1") (pin "92") (pinfunction "GND_92") (pintype "power_in"))
      (node (ref "U$11") (pin "2") (pinfunction "AGND_2") (pintype "bidirectional"))
      (node (ref "U$3") (pin "3") (pinfunction "GND_3") (pintype "bidirectional"))
      (node (ref "U$3") (pin "4") (pinfunction "GND_4") (pintype "bidirectional"))
      (node (ref "U$3") (pin "5") (pinfunction "GND_5") (pintype "bidirectional"))
      (node (ref "U$3") (pin "6") (pinfunction "GND_6") (pintype "bidirectional"))
      (node (ref "U$3") (pin "7") (pinfunction "GND_7") (pintype "bidirectional"))
      (node (ref "U$3") (pin "8") (pinfunction "GND_8") (pintype "bidirectional"))
      (node (ref "U$5") (pin "P$2") (pinfunction "GND_P$2") (pintype "bidirectional"))
      (node (ref "U3") (pin "4") (pinfunction "GND_4") (pintype "bidirectional"))
      (node (ref "U3") (pin "EP") (pinfunction "EP_EP") (pintype "bidirectional"))
      (node (ref "U4") (pin "1") (pinfunction "GND_1") (pintype "bidirectional"))
    )
    (net (code "41") (name "GNDA") (class "Default")
      (node (ref "C1") (pin "2") (pinfunction "2_2") (pintype "passive"))
      (node (ref "C14") (pin "2") (pinfunction "2_2") (pintype "passive"))
      (node (ref "C15") (pin "2") (pinfunction "2_2") (pintype "passive"))
      (node (ref "C16") (pin "2") (pinfunction "2_2") (pintype "passive"))
      (node (ref "C17") (pin "2") (pinfunction "2_2") (pintype "passive"))
      (node (ref "C19") (pin "2") (pinfunction "2_2") (pintype "passive"))
      (node (ref "C2") (pin "C") (pinfunction "-_C") (pintype "passive"))
      (node (ref "IC1") (pin "15") (pinfunction "AVSS_ADC_15") (pintype "bidirectional"))
      (node (ref "IC1") (pin "26") (pinfunction "AVSS_DAC_26") (pintype "bidirectional"))
      (node (ref "IC2") (pin "3") (pinfunction "+IN_3") (pintype "input"))
      (node (ref "IC4") (pin "3") (pinfunction "+IN_3") (pintype "input"))
      (node (ref "J1") (pin "2") (pinfunction "NORM_2") (pintype "bidirectional"))
      (node (ref "J2") (pin "2") (pinfunction "NORM_2") (pintype "bidirectional"))
      (node (ref "J3") (pin "2") (pinfunction "NORM_2") (pintype "bidirectional"))
      (node (ref "J4") (pin "2") (pinfunction "NORM_2") (pintype "bidirectional"))
      (node (ref "R21") (pin "1") (pinfunction "1_1") (pintype "passive"))
      (node (ref "R27") (pin "1") (pinfunction "1_1") (pintype "passive"))
      (node (ref "R31") (pin "1") (pinfunction "1_1") (pintype "passive"))
      (node (ref "U$11") (pin "1") (pinfunction "DGND_1") (pintype "bidirectional"))
      (node (ref "U2") (pin "2") (pinfunction "GND_2") (pintype "input"))
    )
    (net (code "42") (name "Net-(IC1-DIN)") (class "Default")
      (node (ref "IC1") (pin "40") (pinfunction "DIN_40") (pintype "bidirectional"))
      (node (ref "R11") (pin "1") (pinfunction "1_1") (pintype "passive"))
      (node (ref "R13") (pin "1") (pinfunction "1_1") (pintype "passive"))
    )
    (net (code "43") (name "Net-(IC1-DOUT)") (class "Default")
      (node (ref "IC1") (pin "41") (pinfunction "DOUT_41") (pintype "bidirectional"))
      (node (ref "R12") (pin "1") (pinfunction "1_1") (pintype "passive"))
      (node (ref "R14") (pin "1") (pinfunction "1_1") (pintype "passive"))
    )
    (net (code "44") (name "Net-(IC2A--IN)") (class "Default")
      (node (ref "10K") (pin "1") (pinfunction "1_1") (pintype "passive"))
      (node (ref "IC2") (pin "2") (pinfunction "-IN_2") (pintype "input"))
      (node (ref "R17") (pin "2") (pinfunction "2_2") (pintype "passive"))
    )
    (net (code "45") (name "Net-(IC2A-OUT)") (class "Default")
      (node (ref "10K") (pin "2") (pinfunction "2_2") (pintype "passive"))
      (node (ref "IC2") (pin "1") (pinfunction "OUT_1") (pintype "output"))
      (node (ref "R19") (pin "1") (pinfunction "1_1") (pintype "passive"))
    )
    (net (code "46") (name "Net-(IC2B--IN)") (class "Default")
      (node (ref "IC2") (pin "6") (pinfunction "-IN_6") (pintype "input"))
      (node (ref "R18") (pin "1") (pinfunction "1_1") (pintype "passive"))
      (node (ref "R19") (pin "2") (pinfunction "2_2") (pintype "passive"))
    )
    (net (code "47") (name "Net-(IC3A-+IN)") (class "Default")
      (node (ref "IC3") (pin "3") (pinfunction "+IN_3") (pintype "input"))
      (node (ref "R24") (pin "1") (pinfunction "1_1") (pintype "passive"))
      (node (ref "R25") (pin "2") (pinfunction "2_2") (pintype "passive"))
    )
    (net (code "48") (name "Net-(IC3A--IN)") (class "Default")
      (node (ref "IC3") (pin "2") (pinfunction "-IN_2") (pintype "input"))
      (node (ref "R26") (pin "2") (pinfunction "2_2") (pintype "passive"))
      (node (ref "R27") (pin "2") (pinfunction "2_2") (pintype "passive"))
    )
    (net (code "49") (name "Net-(IC3A-OUT)") (class "Default")
      (node (ref "IC3") (pin "1") (pinfunction "OUT_1") (pintype "output"))
      (node (ref "R24") (pin "2") (pinfunction "2_2") (pintype "passive"))
      (node (ref "R34") (pin "1") (pinfunction "1_1") (pintype "passive"))
    )
    (net (code "50") (name "Net-(IC3B-+IN)") (class "Default")
      (node (ref "IC3") (pin "5") (pinfunction "+IN_5") (pintype "input"))
      (node (ref "R28") (pin "1") (pinfunction "1_1") (pintype "passive"))
      (node (ref "R29") (pin "2") (pinfunction "2_2") (pintype "passive"))
    )
    (net (code "51") (name "Net-(IC3B--IN)") (class "Default")
      (node (ref "IC3") (pin "6") (pinfunction "-IN_6") (pintype "input"))
      (node (ref "R30") (pin "2") (pinfunction "2_2") (pintype "passive"))
      (node (ref "R31") (pin "2") (pinfunction "2_2") (pintype "passive"))
    )
    (net (code "52") (name "Net-(IC3B-OUT)") (class "Default")
      (node (ref "IC3") (pin "7") (pinfunction "OUT_7") (pintype "output"))
      (node (ref "R28") (pin "2") (pinfunction "2_2") (pintype "passive"))
      (node (ref "R35") (pin "1") (pinfunction "1_1") (pintype "passive"))
    )
    (net (code "53") (name "Net-(IC4A--IN)") (class "Default")
      (node (ref "IC4") (pin "2") (pinfunction "-IN_2") (pintype "input"))
      (node (ref "R22") (pin "1") (pinfunction "1_1") (pintype "passive"))
      (node (ref "R23") (pin "2") (pinfunction "2_2") (pintype "passive"))
    )
    (net (code "54") (name "Net-(IC4A-OUT)") (class "Default")
      (node (ref "IC4") (pin "1") (pinfunction "OUT_1") (pintype "output"))
      (node (ref "R22") (pin "2") (pinfunction "2_2") (pintype "passive"))
      (node (ref "R33") (pin "1") (pinfunction "1_1") (pintype "passive"))
    )
    (net (code "55") (name "Net-(IC4B--IN)") (class "Default")
      (node (ref "IC4") (pin "6") (pinfunction "-IN_6") (pintype "input"))
      (node (ref "R32") (pin "1") (pinfunction "1_1") (pintype "passive"))
      (node (ref "R33") (pin "2") (pinfunction "2_2") (pintype "passive"))
    )
    (net (code "56") (name "Net-(J1-TIP)") (class "Default")
      (node (ref "J1") (pin "1@1") (pinfunction "RING_1@1") (pintype "bidirectional"))
      (node (ref "J1") (pin "1@2") (pinfunction "RING_1@2") (pintype "bidirectional"))
      (node (ref "J1") (pin "3") (pinfunction "TIP_3") (pintype "bidirectional"))
      (node (ref "R17") (pin "1") (pinfunction "1_1") (pintype "passive"))
    )
    (net (code "57") (name "Net-(J2-TIP)") (class "Default")
      (node (ref "J2") (pin "1@1") (pinfunction "RING_1@1") (pintype "bidirectional"))
      (node (ref "J2") (pin "1@2") (pinfunction "RING_1@2") (pintype "bidirectional"))
      (node (ref "J2") (pin "3") (pinfunction "TIP_3") (pintype "bidirectional"))
      (node (ref "R23") (pin "1") (pinfunction "1_1") (pintype "passive"))
    )
    (net (code "58") (name "Net-(J3-TIP)") (class "Default")
      (node (ref "J3") (pin "1@1") (pinfunction "RING_1@1") (pintype "bidirectional"))
      (node (ref "J3") (pin "1@2") (pinfunction "RING_1@2") (pintype "bidirectional"))
      (node (ref "J3") (pin "3") (pinfunction "TIP_3") (pintype "bidirectional"))
      (node (ref "R35") (pin "2") (pinfunction "2_2") (pintype "passive"))
    )
    (net (code "59") (name "Net-(J4-TIP)") (class "Default")
      (node (ref "J4") (pin "1@1") (pinfunction "RING_1@1") (pintype "bidirectional"))
      (node (ref "J4") (pin "1@2") (pinfunction "RING_1@2") (pintype "bidirectional"))
      (node (ref "J4") (pin "3") (pinfunction "TIP_3") (pintype "bidirectional"))
      (node (ref "R34") (pin "2") (pinfunction "2_2") (pintype "passive"))
    )
    (net (code "60") (name "Net-(LED1-PadC)") (class "Default")
      (node (ref "LED1") (pin "C") (pinfunction "C_C") (pintype "passive"))
      (node (ref "R8") (pin "2") (pinfunction "2_2") (pintype "passive"))
    )
    (net (code "61") (name "Net-(LED2-PadC)") (class "Default")
      (node (ref "LED2") (pin "C") (pinfunction "C_C") (pintype "passive"))
      (node (ref "R9") (pin "2") (pinfunction "2_2") (pintype "passive"))
    )
    (net (code "62") (name "Net-(LED3-BLU)") (class "Default")
      (node (ref "LED3") (pin "B") (pinfunction "BLU_B") (pintype "bidirectional"))
      (node (ref "R6") (pin "2") (pinfunction "2_2") (pintype "passive"))
    )
    (net (code "63") (name "Net-(LED3-GRN)") (class "Default")
      (node (ref "LED3") (pin "G") (pinfunction "GRN_G") (pintype "bidirectional"))
      (node (ref "R7") (pin "2") (pinfunction "2_2") (pintype "passive"))
    )
    (net (code "64") (name "Net-(LED3-RED)") (class "Default")
      (node (ref "LED3") (pin "R") (pinfunction "RED_R") (pintype "bidirectional"))
      (node (ref "R5") (pin "2") (pinfunction "2_2") (pintype "passive"))
    )
    (net (code "65") (name "Net-(U$1-CLKOUT2)") (class "Default")
      (node (ref "R10") (pin "2") (pinfunction "2_2") (pintype "passive"))
      (node (ref "U$1") (pin "87") (pinfunction "CLKOUT2_87") (pintype "input"))
    )
    (net (code "66") (name "Net-(U$5-OUT)") (class "Default")
      (node (ref "R15") (pin "1") (pinfunction "1_1") (pintype "passive"))
      (node (ref "U$5") (pin "P$3") (pinfunction "OUT_P$3") (pintype "bidirectional"))
    )
    (net (code "67") (name "Net-(U3-EN)") (class "Default")
      (node (ref "R2") (pin "2") (pinfunction "2_2") (pintype "passive"))
      (node (ref "U3") (pin "3") (pinfunction "EN_3") (pintype "bidirectional"))
    )
    (net (code "68") (name "Net-(U3-FB)") (class "Default")
      (node (ref "C9") (pin "2") (pinfunction "2_2") (pintype "passive"))
      (node (ref "R3") (pin "2") (pinfunction "2_2") (pintype "passive"))
      (node (ref "R4") (pin "2") (pinfunction "2_2") (pintype "passive"))
      (node (ref "U3") (pin "6") (pinfunction "FB_6") (pintype "bidirectional"))
    )
    (net (code "69") (name "Net-(U3-RON)") (class "Default")
      (node (ref "R1") (pin "2") (pinfunction "2_2") (pintype "passive"))
      (node (ref "U3") (pin "2") (pinfunction "RON_2") (pintype "bidirectional"))
    )
    (net (code "70") (name "Net-(U3-SS)") (class "Default")
      (node (ref "C8") (pin "1") (pinfunction "1_1") (pintype "passive"))
      (node (ref "U3") (pin "5") (pinfunction "SS_5") (pintype "bidirectional"))
    )
    (net (code "71") (name "VDD") (class "Default")
      (node (ref "C14") (pin "1") (pinfunction "1_1") (pintype "passive"))
      (node (ref "C15") (pin "1") (pinfunction "1_1") (pintype "passive"))
      (node (ref "C16") (pin "1") (pinfunction "1_1") (pintype "passive"))
      (node (ref "C17") (pin "1") (pinfunction "1_1") (pintype "passive"))
      (node (ref "C2") (pin "A") (pinfunction "+_A") (pintype "passive"))
      (node (ref "IC1") (pin "16") (pinfunction "DRVDD_16") (pintype "bidirectional"))
      (node (ref "IC1") (pin "17") (pinfunction "DRVDD_17") (pintype "bidirectional"))
      (node (ref "IC1") (pin "24") (pinfunction "DRVDD_24") (pintype "bidirectional"))
      (node (ref "IC1") (pin "25") (pinfunction "AVDD_DAC_25") (pintype "bidirectional"))
      (node (ref "U2") (pin "3") (pinfunction "OUT_3") (pintype "output"))
    )
    (net (code "72") (name "unconnected-(IC1-GPIO1-Pad35)") (class "Default")
      (node (ref "IC1") (pin "35") (pinfunction "GPIO1_35") (pintype "bidirectional"))
    )
    (net (code "73") (name "unconnected-(IC1-GPIO2-Pad34)") (class "Default")
      (node (ref "IC1") (pin "34") (pinfunction "GPIO2_34") (pintype "bidirectional"))
    )
    (net (code "74") (name "unconnected-(IC1-LEFT_LOM-Pad30)") (class "Default")
      (node (ref "IC1") (pin "30") (pinfunction "LEFT_LOM_30") (pintype "bidirectional"))
    )
    (net (code "75") (name "unconnected-(IC1-LEFT_LOP-Pad29)") (class "Default")
      (node (ref "IC1") (pin "29") (pinfunction "LEFT_LOP_29") (pintype "bidirectional"))
    )
    (net (code "76") (name "unconnected-(IC1-LINE2LM-Pad8)") (class "Default")
      (node (ref "IC1") (pin "8") (pinfunction "LINE2LM_8") (pintype "bidirectional"))
    )
    (net (code "77") (name "unconnected-(IC1-LINE2LP-Pad7)") (class "Default")
      (node (ref "IC1") (pin "7") (pinfunction "LINE2LP_7") (pintype "bidirectional"))
    )
    (net (code "78") (name "unconnected-(IC1-LINE2RM-Pad10)") (class "Default")
      (node (ref "IC1") (pin "10") (pinfunction "LINE2RM_10") (pintype "bidirectional"))
    )
    (net (code "79") (name "unconnected-(IC1-LINE2RP-Pad9)") (class "Default")
      (node (ref "IC1") (pin "9") (pinfunction "LINE2RP_9") (pintype "bidirectional"))
    )
    (net (code "80") (name "unconnected-(IC1-MFP2-Pad47)") (class "Default")
      (node (ref "IC1") (pin "47") (pinfunction "MFP2_47") (pintype "bidirectional"))
    )
    (net (code "81") (name "unconnected-(IC1-MFP3-Pad48)") (class "Default")
      (node (ref "IC1") (pin "48") (pinfunction "MFP3_48") (pintype "bidirectional"))
    )
    (net (code "82") (name "unconnected-(IC1-MIC3L-Pad11)") (class "Default")
      (node (ref "IC1") (pin "11") (pinfunction "MIC3L_11") (pintype "bidirectional"))
    )
    (net (code "83") (name "unconnected-(IC1-MIC3R-Pad14)") (class "Default")
      (node (ref "IC1") (pin "14") (pinfunction "MIC3R_14") (pintype "bidirectional"))
    )
    (net (code "84") (name "unconnected-(IC1-MICDET-Pad12)") (class "Default")
      (node (ref "IC1") (pin "12") (pinfunction "MICDET_12") (pintype "bidirectional"))
    )
    (net (code "85") (name "unconnected-(IC1-MONO_LOM-Pad28)") (class "Default")
      (node (ref "IC1") (pin "28") (pinfunction "MONO_LOM_28") (pintype "bidirectional"))
    )
    (net (code "86") (name "unconnected-(IC1-MONO_LOP-Pad27)") (class "Default")
      (node (ref "IC1") (pin "27") (pinfunction "MONO_LOP_27") (pintype "bidirectional"))
    )
    (net (code "87") (name "unconnected-(IC1-RIGHT_LOM-Pad32)") (class "Default")
      (node (ref "IC1") (pin "32") (pinfunction "RIGHT_LOM_32") (pintype "bidirectional"))
    )
    (net (code "88") (name "unconnected-(IC1-RIGHT_LOP-Pad31)") (class "Default")
      (node (ref "IC1") (pin "31") (pinfunction "RIGHT_LOP_31") (pintype "bidirectional"))
    )
    (net (code "89") (name "unconnected-(U$1-AIN4-Pad79)") (class "Default")
      (node (ref "U$1") (pin "79") (pinfunction "AIN4_79") (pintype "passive"))
    )
    (net (code "90") (name "unconnected-(U$1-AIN5-Pad82)") (class "Default")
      (node (ref "U$1") (pin "82") (pinfunction "AIN5_82") (pintype "passive"))
    )
    (net (code "91") (name "unconnected-(U$1-AIN6-Pad81)") (class "Default")
      (node (ref "U$1") (pin "81") (pinfunction "AIN6_81") (pintype "passive"))
    )
    (net (code "92") (name "unconnected-(U$1-EHRPWM2A-Pad19)") (class "Default")
      (node (ref "U$1") (pin "19") (pinfunction "EHRPWM2A_19") (pintype "passive"))
    )
    (net (code "93") (name "unconnected-(U$1-EHRPWM2B-Pad13)") (class "Default")
      (node (ref "U$1") (pin "13") (pinfunction "EHRPWM2B_13") (pintype "passive"))
    )
    (net (code "94") (name "unconnected-(U$1-GPIO0_26-Pad14)") (class "Default")
      (node (ref "U$1") (pin "14") (pinfunction "GPIO0_26_14") (pintype "passive"))
    )
    (net (code "95") (name "unconnected-(U$1-GPIO0_27-Pad17)") (class "Default")
      (node (ref "U$1") (pin "17") (pinfunction "GPIO0_27_17") (pintype "passive"))
    )
    (net (code "96") (name "unconnected-(U$1-GPIO1_0-Pad25)") (class "Default")
      (node (ref "U$1") (pin "25") (pinfunction "GPIO1_0_25") (pintype "passive"))
    )
    (net (code "97") (name "unconnected-(U$1-GPIO1_1-Pad24)") (class "Default")
      (node (ref "U$1") (pin "24") (pinfunction "GPIO1_1_24") (pintype "passive"))
    )
    (net (code "98") (name "unconnected-(U$1-GPIO1_2-Pad5)") (class "Default")
      (node (ref "U$1") (pin "5") (pinfunction "GPIO1_2_5") (pintype "passive"))
    )
    (net (code "99") (name "unconnected-(U$1-GPIO1_3-Pad6)") (class "Default")
      (node (ref "U$1") (pin "6") (pinfunction "GPIO1_3_6") (pintype "passive"))
    )
    (net (code "100") (name "unconnected-(U$1-GPIO1_4-Pad23)") (class "Default")
      (node (ref "U$1") (pin "23") (pinfunction "GPIO1_4_23") (pintype "passive"))
    )
    (net (code "101") (name "unconnected-(U$1-GPIO1_5-Pad22)") (class "Default")
      (node (ref "U$1") (pin "22") (pinfunction "GPIO1_5_22") (pintype "passive"))
    )
    (net (code "102") (name "unconnected-(U$1-GPIO1_6-Pad3)") (class "Default")
      (node (ref "U$1") (pin "3") (pinfunction "GPIO1_6_3") (pintype "passive"))
    )
    (net (code "103") (name "unconnected-(U$1-GPIO1_7-Pad4)") (class "Default")
      (node (ref "U$1") (pin "4") (pinfunction "GPIO1_7_4") (pintype "passive"))
    )
    (net (code "104") (name "unconnected-(U$1-GPIO1_12-Pad12)") (class "Default")
      (node (ref "U$1") (pin "12") (pinfunction "GPIO1_12_12") (pintype "passive"))
    )
    (net (code "105") (name "unconnected-(U$1-GPIO1_13-Pad11)") (class "Default")
      (node (ref "U$1") (pin "11") (pinfunction "GPIO1_13_11") (pintype "passive"))
    )
    (net (code "106") (name "unconnected-(U$1-GPIO1_14-Pad16)") (class "Default")
      (node (ref "U$1") (pin "16") (pinfunction "GPIO1_14_16") (pintype "passive"))
    )
    (net (code "107") (name "unconnected-(U$1-GPIO1_15-Pad15)") (class "Default")
      (node (ref "U$1") (pin "15") (pinfunction "GPIO1_15_15") (pintype "passive"))
    )
    (net (code "108") (name "unconnected-(U$1-GPIO1_29-Pad26)") (class "Default")
      (node (ref "U$1") (pin "26") (pinfunction "GPIO1_29_26") (pintype "passive"))
    )
    (net (code "109") (name "unconnected-(U$1-GPIO1_30-Pad21)") (class "Default")
      (node (ref "U$1") (pin "21") (pinfunction "GPIO1_30_21") (pintype "passive"))
    )
    (net (code "110") (name "unconnected-(U$1-GPIO1_31-Pad20)") (class "Default")
      (node (ref "U$1") (pin "20") (pinfunction "GPIO1_31_20") (pintype "passive"))
    )
    (net (code "111") (name "unconnected-(U$1-GPIO2_1-Pad18)") (class "Default")
      (node (ref "U$1") (pin "18") (pinfunction "GPIO2_1_18") (pintype "passive"))
    )
    (net (code "112") (name "unconnected-(U$1-GPIO2_6-Pad45)") (class "Default")
      (node (ref "U$1") (pin "45") (pinfunction "GPIO2_6_45") (pintype "passive"))
    )
    (net (code "113") (name "unconnected-(U$1-GPIO2_7-Pad46)") (class "Default")
      (node (ref "U$1") (pin "46") (pinfunction "GPIO2_7_46") (pintype "passive"))
    )
    (net (code "114") (name "unconnected-(U$1-GPIO2_8-Pad43)") (class "Default")
      (node (ref "U$1") (pin "43") (pinfunction "GPIO2_8_43") (pintype "passive"))
    )
    (net (code "115") (name "unconnected-(U$1-GPIO2_9-Pad44)") (class "Default")
      (node (ref "U$1") (pin "44") (pinfunction "GPIO2_9_44") (pintype "passive"))
    )
    (net (code "116") (name "unconnected-(U$1-GPIO2_10-Pad41)") (class "Default")
      (node (ref "U$1") (pin "41") (pinfunction "GPIO2_10_41") (pintype "passive"))
    )
    (net (code "117") (name "unconnected-(U$1-GPIO2_11-Pad42)") (class "Default")
      (node (ref "U$1") (pin "42") (pinfunction "GPIO2_11_42") (pintype "passive"))
    )
    (net (code "118") (name "unconnected-(U$1-GPIO2_12-Pad39)") (class "Default")
      (node (ref "U$1") (pin "39") (pinfunction "GPIO2_12_39") (pintype "passive"))
    )
    (net (code "119") (name "unconnected-(U$1-GPIO2_13-Pad40)") (class "Default")
      (node (ref "U$1") (pin "40") (pinfunction "GPIO2_13_40") (pintype "passive"))
    )
    (net (code "120") (name "unconnected-(U$1-GPIO2_22-Pad27)") (class "Default")
      (node (ref "U$1") (pin "27") (pinfunction "GPIO2_22_27") (pintype "passive"))
    )
    (net (code "121") (name "unconnected-(U$1-GPIO2_23-Pad29)") (class "Default")
      (node (ref "U$1") (pin "29") (pinfunction "GPIO2_23_29") (pintype "passive"))
    )
    (net (code "122") (name "unconnected-(U$1-GPIO2_24-Pad28)") (class "Default")
      (node (ref "U$1") (pin "28") (pinfunction "GPIO2_24_28") (pintype "passive"))
    )
    (net (code "123") (name "unconnected-(U$1-GPIO2_25-Pad30)") (class "Default")
      (node (ref "U$1") (pin "30") (pinfunction "GPIO2_25_30") (pintype "passive"))
    )
    (net (code "124") (name "unconnected-(U$1-I2C2_SCL-Pad65)") (class "Default")
      (node (ref "U$1") (pin "65") (pinfunction "I2C2_SCL_65") (pintype "passive"))
    )
    (net (code "125") (name "unconnected-(U$1-I2C2_SDA-Pad66)") (class "Default")
      (node (ref "U$1") (pin "66") (pinfunction "I2C2_SDA_66") (pintype "passive"))
    )
    (net (code "126") (name "unconnected-(U$1-PWR_BUT-Pad55)") (class "Default")
      (node (ref "U$1") (pin "55") (pinfunction "PWR_BUT_55") (pintype "passive"))
    )
    (net (code "127") (name "unconnected-(U$1-SPI1_DI-Pad76)") (class "Default")
      (node (ref "U$1") (pin "76") (pinfunction "SPI1_DI_76") (pintype "passive"))
    )
    (net (code "128") (name "unconnected-(U$1-SYS_5V-Pad54)") (class "Default")
      (node (ref "U$1") (pin "54") (pinfunction "SYS_5V_54") (pintype "passive"))
    )
    (net (code "129") (name "unconnected-(U$1-SYS_RESETN-Pad56)") (class "Default")
      (node (ref "U$1") (pin "56") (pinfunction "SYS_RESETN_56") (pintype "passive"))
    )
    (net (code "130") (name "unconnected-(U$1-TIMER4-Pad7)") (class "Default")
      (node (ref "U$1") (pin "7") (pinfunction "TIMER4_7") (pintype "passive"))
    )
    (net (code "131") (name "unconnected-(U$1-TIMER5-Pad9)") (class "Default")
      (node (ref "U$1") (pin "9") (pinfunction "TIMER5_9") (pintype "passive"))
    )
    (net (code "132") (name "unconnected-(U$1-TIMER6-Pad10)") (class "Default")
      (node (ref "U$1") (pin "10") (pinfunction "TIMER6_10") (pintype "passive"))
    )
    (net (code "133") (name "unconnected-(U$1-TIMER7-Pad8)") (class "Default")
      (node (ref "U$1") (pin "8") (pinfunction "TIMER7_8") (pintype "passive"))
    )
    (net (code "134") (name "unconnected-(U$1-UART1_RXD-Pad72)") (class "Default")
      (node (ref "U$1") (pin "72") (pinfunction "UART1_RXD_72") (pintype "passive"))
    )
    (net (code "135") (name "unconnected-(U$1-UART1_TXD-Pad70)") (class "Default")
      (node (ref "U$1") (pin "70") (pinfunction "UART1_TXD_70") (pintype "passive"))
    )
    (net (code "136") (name "unconnected-(U$1-UART2_TXD-Pad67)") (class "Default")
      (node (ref "U$1") (pin "67") (pinfunction "UART2_TXD_67") (pintype "passive"))
    )
    (net (code "137") (name "unconnected-(U$1-UART3_CTSN-Pad36)") (class "Default")
      (node (ref "U$1") (pin "36") (pinfunction "UART3_CTSN_36") (pintype "passive"))
    )
    (net (code "138") (name "unconnected-(U$1-UART3_RTSN-Pad34)") (class "Default")
      (node (ref "U$1") (pin "34") (pinfunction "UART3_RTSN_34") (pintype "passive"))
    )
    (net (code "139") (name "unconnected-(U$1-UART4_CTSN-Pad35)") (class "Default")
      (node (ref "U$1") (pin "35") (pinfunction "UART4_CTSN_35") (pintype "passive"))
    )
    (net (code "140") (name "unconnected-(U$1-UART4_RTSN-Pad33)") (class "Default")
      (node (ref "U$1") (pin "33") (pinfunction "UART4_RTSN_33") (pintype "passive"))
    )
    (net (code "141") (name "unconnected-(U$1-UART5_CTSN-Pad31)") (class "Default")
      (node (ref "U$1") (pin "31") (pinfunction "UART5_CTSN_31") (pintype "passive"))
    )
    (net (code "142") (name "unconnected-(U$1-UART5_RTSN-Pad32)") (class "Default")
      (node (ref "U$1") (pin "32") (pinfunction "UART5_RTSN_32") (pintype "passive"))
    )
    (net (code "143") (name "unconnected-(U$1-UART5_RXD-Pad38)") (class "Default")
      (node (ref "U$1") (pin "38") (pinfunction "UART5_RXD_38") (pintype "passive"))
    )
    (net (code "144") (name "unconnected-(U$1-UART5_TXD-Pad37)") (class "Default")
      (node (ref "U$1") (pin "37") (pinfunction "UART5_TXD_37") (pintype "passive"))
    )
    (net (code "145") (name "unconnected-(U$5-EN-PadP$1)") (class "Default")
      (node (ref "U$5") (pin "P$1") (pinfunction "EN_P$1") (pintype "bidirectional"))
    )
    (net (code "146") (name "unconnected-(U$11-IN-Pad3)") (class "Default")
      (node (ref "U$11") (pin "3") (pinfunction "IN_3") (pintype "bidirectional"))
    )
  )
)
